# Photodiode.net
KiCad netlist of a schematic drawn in Altium Designer
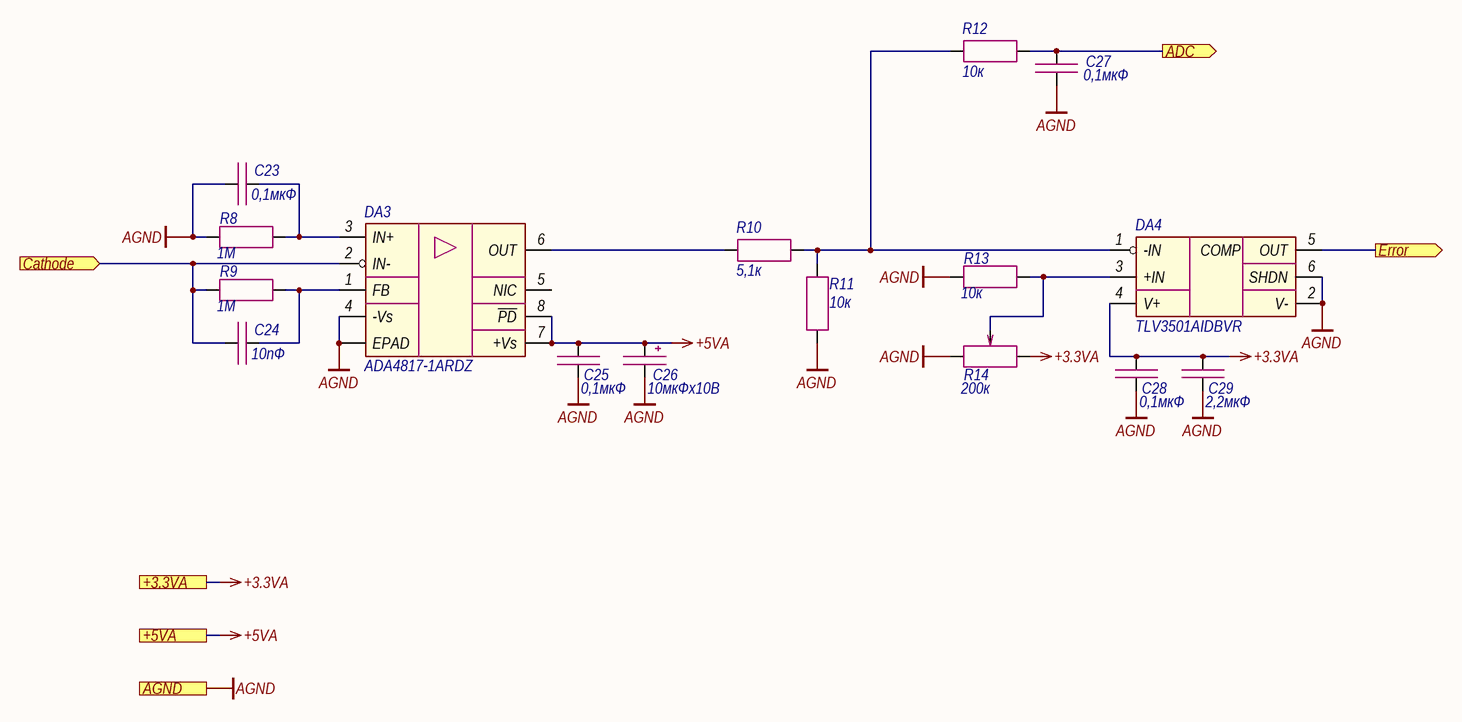
[diagram p0: Photodiode.SchDoc]

(export (version "E")
  (design (tool "Eeschema 10.0.6"))
  (components
    (comp (ref "C23")
      (value "0,1мкФ")
      (footprint "Pcb_library:CAP_0603")
      (fields (field (name "MANUFACTURER") "Murata"))
      (libsource (lib "Schem_library") (part "Capacitor"))
    )
    (comp (ref "C24")
      (value "10пФ")
      (footprint "Pcb_library:CAP_0603")
      (fields (field (name "MANUFACTURER") "Murata"))
      (libsource (lib "Schem_library") (part "Capacitor"))
    )
    (comp (ref "C25")
      (value "0,1мкФ")
      (footprint "Pcb_library:CAP_0603")
      (fields (field (name "MANUFACTURER") "Murata"))
      (libsource (lib "Schem_library") (part "Capacitor"))
    )
    (comp (ref "C26")
      (value "10мкФх10B")
      (footprint "Pcb_library:CAP_A")
      (libsource (lib "Schem_library") (part "Capacitor_Polar"))
    )
    (comp (ref "C27")
      (value "0,1мкФ")
      (footprint "Pcb_library:CAP_0603")
      (fields (field (name "MANUFACTURER") "Murata"))
      (libsource (lib "Schem_library") (part "Capacitor"))
    )
    (comp (ref "C28")
      (value "0,1мкФ")
      (footprint "Pcb_library:CAP_0603")
      (fields (field (name "MANUFACTURER") "Murata"))
      (libsource (lib "Schem_library") (part "Capacitor"))
    )
    (comp (ref "C29")
      (value "2,2мкФ")
      (footprint "Pcb_library:CAP_0603")
      (fields (field (name "MANUFACTURER") "Murata"))
      (libsource (lib "Schem_library") (part "Capacitor"))
    )
    (comp (ref "DA3")
      (value "ADA4817-1ARDZ")
      (footprint "Pcb_library:SOIC-8 EPAD")
      (fields (field (name "MANUFACTURER") "Analog Devices"))
      (libsource (lib "Schem_library") (part "ADA4817-1ARDZ"))
    )
    (comp (ref "DA4")
      (value "TLV3501AIDBVR")
      (footprint "Pcb_library:SOT-23-6")
      (fields (field (name "MANUFACTURER") "Texas Instruments"))
      (libsource (lib "Schem_library") (part "TLV3501"))
    )
    (comp (ref "R8")
      (value "1М")
      (footprint "Pcb_library:RES_0805")
      (fields (field (name "MANUFACTURER") "Yageo"))
      (libsource (lib "Schem_library") (part "Resistor"))
    )
    (comp (ref "R9")
      (value "1М")
      (footprint "Pcb_library:RES_0805")
      (fields (field (name "MANUFACTURER") "Yageo"))
      (libsource (lib "Schem_library") (part "Resistor"))
    )
    (comp (ref "R10")
      (value "5,1к")
      (footprint "Pcb_library:RES_0603")
      (fields (field (name "MANUFACTURER") "Yageo"))
      (libsource (lib "Schem_library") (part "Resistor"))
    )
    (comp (ref "R11")
      (value "10к")
      (footprint "Pcb_library:RES_0603")
      (fields (field (name "MANUFACTURER") "Yageo"))
      (libsource (lib "Schem_library") (part "Resistor"))
    )
    (comp (ref "R12")
      (value "10к")
      (footprint "Pcb_library:RES_0603")
      (fields (field (name "MANUFACTURER") "Yageo"))
      (libsource (lib "Schem_library") (part "Resistor"))
    )
    (comp (ref "R13")
      (value "10к")
      (footprint "Pcb_library:RES_0603")
      (fields (field (name "MANUFACTURER") "Yageo"))
      (libsource (lib "Schem_library") (part "Resistor"))
    )
    (comp (ref "R14")
      (value "200к")
      (footprint "Pcb_library:3224W")
      (fields (field (name "MANUFACTURER") "Bourns"))
      (libsource (lib "Schem_library") (part "Resistor_Variable"))
    )
  )
  (nets
    (net (code "1") (name "+3.3VA") (class "Default")
      (node (ref "C28") (pin "1") (pinfunction "1_1") (pintype "passive"))
      (node (ref "C29") (pin "1") (pinfunction "1_1") (pintype "passive"))
      (node (ref "DA4") (pin "4") (pinfunction "V+_4") (pintype "passive"))
      (node (ref "R14") (pin "3") (pintype "passive"))
    )
    (net (code "2") (name "+5VA") (class "Default")
      (node (ref "C25") (pin "1") (pinfunction "1_1") (pintype "passive"))
      (node (ref "C26") (pin "1") (pinfunction "1_1") (pintype "passive"))
      (node (ref "DA3") (pin "7") (pinfunction "+Vs_7") (pintype "passive"))
      (node (ref "DA3") (pin "8") (pinfunction "~{PD}_8") (pintype "passive"))
    )
    (net (code "3") (name "/ADC") (class "Default")
      (node (ref "C27") (pin "1") (pinfunction "1_1") (pintype "passive"))
      (node (ref "R12") (pin "2") (pinfunction "2_2") (pintype "passive"))
    )
    (net (code "4") (name "/Cathode") (class "Default")
      (node (ref "C24") (pin "2") (pinfunction "2_2") (pintype "passive"))
      (node (ref "DA3") (pin "2") (pinfunction "IN-_2") (pintype "passive"))
      (node (ref "R9") (pin "2") (pinfunction "2_2") (pintype "passive"))
    )
    (net (code "5") (name "/Error") (class "Default")
      (node (ref "DA4") (pin "5") (pinfunction "OUT_5") (pintype "passive"))
    )
    (net (code "6") (name "AGND") (class "Default")
      (node (ref "C23") (pin "1") (pinfunction "1_1") (pintype "passive"))
      (node (ref "C25") (pin "2") (pinfunction "2_2") (pintype "passive"))
      (node (ref "C26") (pin "2") (pinfunction "2_2") (pintype "passive"))
      (node (ref "C27") (pin "2") (pinfunction "2_2") (pintype "passive"))
      (node (ref "C28") (pin "2") (pinfunction "2_2") (pintype "passive"))
      (node (ref "C29") (pin "2") (pinfunction "2_2") (pintype "passive"))
      (node (ref "DA3") (pin "4") (pinfunction "-Vs_4") (pintype "passive"))
      (node (ref "DA3") (pin "EPAD") (pinfunction "EPAD_EPAD") (pintype "passive"))
      (node (ref "DA4") (pin "2") (pinfunction "V-_2") (pintype "passive"))
      (node (ref "DA4") (pin "6") (pinfunction "SHDN_6") (pintype "passive"))
      (node (ref "R11") (pin "2") (pinfunction "2_2") (pintype "passive"))
      (node (ref "R13") (pin "1") (pinfunction "1_1") (pintype "passive"))
      (node (ref "R14") (pin "1") (pintype "passive"))
      (node (ref "R8") (pin "2") (pinfunction "2_2") (pintype "passive"))
    )
    (net (code "7") (name "Net-(DA3-FB)") (class "Default")
      (node (ref "C24") (pin "1") (pinfunction "1_1") (pintype "passive"))
      (node (ref "DA3") (pin "1") (pinfunction "FB_1") (pintype "passive"))
      (node (ref "R9") (pin "1") (pinfunction "1_1") (pintype "passive"))
    )
    (net (code "8") (name "Net-(DA3-IN+)") (class "Default")
      (node (ref "C23") (pin "2") (pinfunction "2_2") (pintype "passive"))
      (node (ref "DA3") (pin "3") (pinfunction "IN+_3") (pintype "passive"))
      (node (ref "R8") (pin "1") (pinfunction "1_1") (pintype "passive"))
    )
    (net (code "9") (name "Net-(DA3-OUT)") (class "Default")
      (node (ref "DA3") (pin "6") (pinfunction "OUT_6") (pintype "passive"))
      (node (ref "R10") (pin "1") (pinfunction "1_1") (pintype "passive"))
    )
    (net (code "10") (name "Net-(DA4-+IN)") (class "Default")
      (node (ref "DA4") (pin "3") (pinfunction "+IN_3") (pintype "passive"))
      (node (ref "R13") (pin "2") (pinfunction "2_2") (pintype "passive"))
      (node (ref "R14") (pin "2") (pintype "passive"))
    )
    (net (code "11") (name "Net-(DA4--IN)") (class "Default")
      (node (ref "DA4") (pin "1") (pinfunction "-IN_1") (pintype "passive"))
      (node (ref "R10") (pin "2") (pinfunction "2_2") (pintype "passive"))
      (node (ref "R11") (pin "1") (pinfunction "1_1") (pintype "passive"))
      (node (ref "R12") (pin "1") (pinfunction "1_1") (pintype "passive"))
    )
    (net (code "12") (name "unconnected-(DA3-NIC-Pad5)") (class "Default")
      (node (ref "DA3") (pin "5") (pinfunction "NIC_5") (pintype "passive"))
    )
  )
)
